# 8chADC_V2.net
KiCad netlist of a schematic drawn in EAGLE
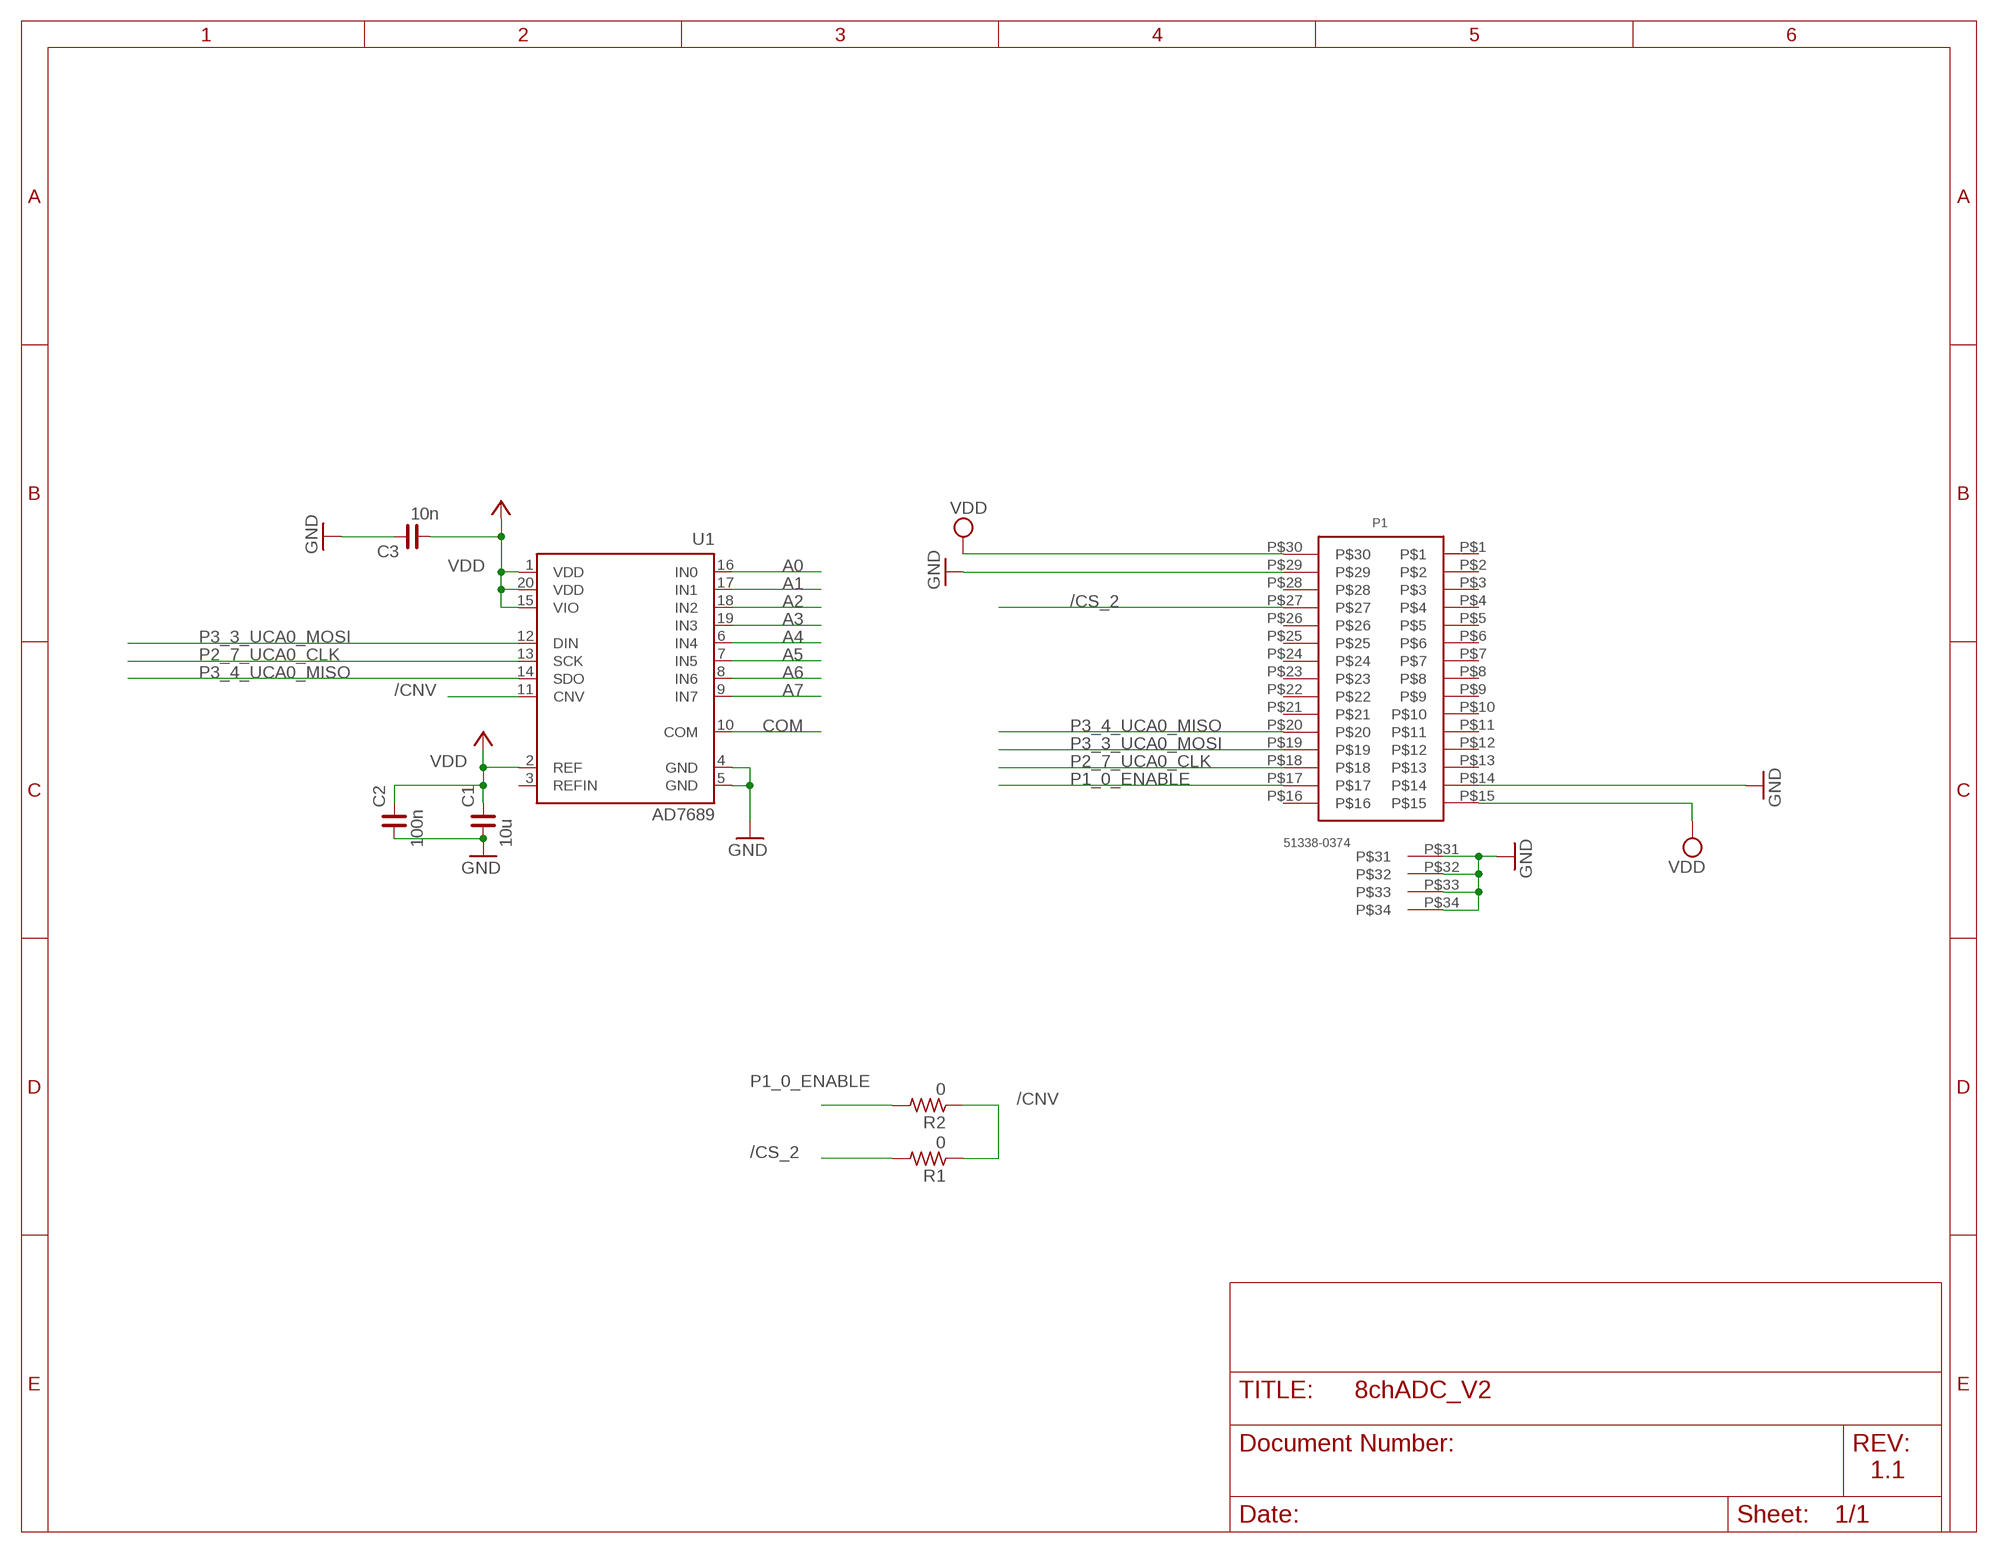
[diagram p0: schematic, sheet 1]

(export (version "E")
  (design (tool "Eeschema 10.0.6"))
  (components
    (comp (ref "C1")
      (value "10u")
      (footprint "eagle-import:C0402")
      (libsource (lib "eagle-import") (part "C_0402"))
    )
    (comp (ref "C2")
      (value "100n")
      (footprint "eagle-import:C0402")
      (libsource (lib "eagle-import") (part "C_0402"))
    )
    (comp (ref "C3")
      (value "10n")
      (footprint "eagle-import:C0402")
      (libsource (lib "eagle-import") (part "C_0402"))
    )
    (comp (ref "P1")
      (value "51338-0374")
      (footprint "eagle-import:51338-0374_RECEPTACLE")
      (libsource (lib "eagle-import") (part "51338-0374_RECEPTACLE"))
    )
    (comp (ref "R1")
      (value "0")
      (footprint "eagle-import:R0402")
      (libsource (lib "eagle-import") (part "R_0402"))
    )
    (comp (ref "R2")
      (value "0")
      (footprint "eagle-import:R0402")
      (libsource (lib "eagle-import") (part "R_0402"))
    )
    (comp (ref "U1")
      (value "AD7689")
      (footprint "eagle-import:LFCSP20")
      (libsource (lib "eagle-import") (part "AD7689"))
    )
  )
  (nets
    (net (code "1") (name "+3V3") (class "Default")
      (node (ref "C1") (pin "2") (pinfunction "2_2") (pintype "passive"))
      (node (ref "C2") (pin "2") (pinfunction "2_2") (pintype "passive"))
      (node (ref "C3") (pin "1") (pinfunction "1_1") (pintype "passive"))
      (node (ref "P1") (pin "P$15") (pinfunction "P$15_P$15") (pintype "bidirectional"))
      (node (ref "P1") (pin "P$30") (pinfunction "P$30_P$30") (pintype "bidirectional"))
      (node (ref "U1") (pin "1") (pinfunction "VDD_1") (pintype "power_in"))
      (node (ref "U1") (pin "15") (pinfunction "VIO_15") (pintype "power_in"))
      (node (ref "U1") (pin "2") (pinfunction "REF_2") (pintype "bidirectional"))
      (node (ref "U1") (pin "20") (pinfunction "VDD_20") (pintype "power_in"))
    )
    (net (code "2") (name "/A0") (class "Default")
      (node (ref "U1") (pin "16") (pinfunction "IN0_16") (pintype "input"))
    )
    (net (code "3") (name "/A1") (class "Default")
      (node (ref "U1") (pin "17") (pinfunction "IN1_17") (pintype "input"))
    )
    (net (code "4") (name "/A2") (class "Default")
      (node (ref "U1") (pin "18") (pinfunction "IN2_18") (pintype "input"))
    )
    (net (code "5") (name "/A3") (class "Default")
      (node (ref "U1") (pin "19") (pinfunction "IN3_19") (pintype "input"))
    )
    (net (code "6") (name "/A4") (class "Default")
      (node (ref "U1") (pin "6") (pinfunction "IN4_6") (pintype "input"))
    )
    (net (code "7") (name "/A5") (class "Default")
      (node (ref "U1") (pin "7") (pinfunction "IN5_7") (pintype "input"))
    )
    (net (code "8") (name "/A6") (class "Default")
      (node (ref "U1") (pin "8") (pinfunction "IN6_8") (pintype "input"))
    )
    (net (code "9") (name "/A7") (class "Default")
      (node (ref "U1") (pin "9") (pinfunction "IN7_9") (pintype "input"))
    )
    (net (code "10") (name "/COM") (class "Default")
      (node (ref "U1") (pin "10") (pinfunction "COM_10") (pintype "input"))
    )
    (net (code "11") (name "/P1_0_ENABLE") (class "Default")
      (node (ref "P1") (pin "P$17") (pinfunction "P$17_P$17") (pintype "bidirectional"))
      (node (ref "R2") (pin "2") (pinfunction "2_2") (pintype "passive"))
    )
    (net (code "12") (name "/P2_7_UCA0_CLK") (class "Default")
      (node (ref "P1") (pin "P$18") (pinfunction "P$18_P$18") (pintype "bidirectional"))
      (node (ref "U1") (pin "13") (pinfunction "SCK_13") (pintype "input"))
    )
    (net (code "13") (name "/P3_3_UCA0_MOSI") (class "Default")
      (node (ref "P1") (pin "P$19") (pinfunction "P$19_P$19") (pintype "bidirectional"))
      (node (ref "U1") (pin "12") (pinfunction "DIN_12") (pintype "input"))
    )
    (net (code "14") (name "/P3_4_UCA0_MISO") (class "Default")
      (node (ref "P1") (pin "P$20") (pinfunction "P$20_P$20") (pintype "bidirectional"))
      (node (ref "U1") (pin "14") (pinfunction "SDO_14") (pintype "output"))
    )
    (net (code "15") (name "/{slash}CNV") (class "Default")
      (node (ref "R1") (pin "1") (pinfunction "1_1") (pintype "passive"))
      (node (ref "R2") (pin "1") (pinfunction "1_1") (pintype "passive"))
      (node (ref "U1") (pin "11") (pinfunction "CNV_11") (pintype "input"))
    )
    (net (code "16") (name "/{slash}CS_2") (class "Default")
      (node (ref "P1") (pin "P$27") (pinfunction "P$27_P$27") (pintype "bidirectional"))
      (node (ref "R1") (pin "2") (pinfunction "2_2") (pintype "passive"))
    )
    (net (code "17") (name "GND") (class "Default")
      (node (ref "C1") (pin "1") (pinfunction "1_1") (pintype "passive"))
      (node (ref "C2") (pin "1") (pinfunction "1_1") (pintype "passive"))
      (node (ref "C3") (pin "2") (pinfunction "2_2") (pintype "passive"))
      (node (ref "P1") (pin "P$14") (pinfunction "P$14_P$14") (pintype "bidirectional"))
      (node (ref "P1") (pin "P$29") (pinfunction "P$29_P$29") (pintype "bidirectional"))
      (node (ref "P1") (pin "P$31") (pinfunction "P$31_P$31") (pintype "bidirectional"))
      (node (ref "P1") (pin "P$32") (pinfunction "P$32_P$32") (pintype "bidirectional"))
      (node (ref "P1") (pin "P$33") (pinfunction "P$33_P$33") (pintype "bidirectional"))
      (node (ref "P1") (pin "P$34") (pinfunction "P$34_P$34") (pintype "bidirectional"))
      (node (ref "U1") (pin "4") (pinfunction "GND_4") (pintype "power_in"))
      (node (ref "U1") (pin "5") (pinfunction "GND_5") (pintype "power_in"))
    )
    (net (code "18") (name "unconnected-(P1-PadP$1)") (class "Default")
      (node (ref "P1") (pin "P$1") (pinfunction "P$1_P$1") (pintype "bidirectional"))
    )
    (net (code "19") (name "unconnected-(P1-PadP$2)") (class "Default")
      (node (ref "P1") (pin "P$2") (pinfunction "P$2_P$2") (pintype "bidirectional"))
    )
    (net (code "20") (name "unconnected-(P1-PadP$3)") (class "Default")
      (node (ref "P1") (pin "P$3") (pinfunction "P$3_P$3") (pintype "bidirectional"))
    )
    (net (code "21") (name "unconnected-(P1-PadP$4)") (class "Default")
      (node (ref "P1") (pin "P$4") (pinfunction "P$4_P$4") (pintype "bidirectional"))
    )
    (net (code "22") (name "unconnected-(P1-PadP$5)") (class "Default")
      (node (ref "P1") (pin "P$5") (pinfunction "P$5_P$5") (pintype "bidirectional"))
    )
    (net (code "23") (name "unconnected-(P1-PadP$6)") (class "Default")
      (node (ref "P1") (pin "P$6") (pinfunction "P$6_P$6") (pintype "bidirectional"))
    )
    (net (code "24") (name "unconnected-(P1-PadP$7)") (class "Default")
      (node (ref "P1") (pin "P$7") (pinfunction "P$7_P$7") (pintype "bidirectional"))
    )
    (net (code "25") (name "unconnected-(P1-PadP$8)") (class "Default")
      (node (ref "P1") (pin "P$8") (pinfunction "P$8_P$8") (pintype "bidirectional"))
    )
    (net (code "26") (name "unconnected-(P1-PadP$9)") (class "Default")
      (node (ref "P1") (pin "P$9") (pinfunction "P$9_P$9") (pintype "bidirectional"))
    )
    (net (code "27") (name "unconnected-(P1-PadP$10)") (class "Default")
      (node (ref "P1") (pin "P$10") (pinfunction "P$10_P$10") (pintype "bidirectional"))
    )
    (net (code "28") (name "unconnected-(P1-PadP$11)") (class "Default")
      (node (ref "P1") (pin "P$11") (pinfunction "P$11_P$11") (pintype "bidirectional"))
    )
    (net (code "29") (name "unconnected-(P1-PadP$12)") (class "Default")
      (node (ref "P1") (pin "P$12") (pinfunction "P$12_P$12") (pintype "bidirectional"))
    )
    (net (code "30") (name "unconnected-(P1-PadP$13)") (class "Default")
      (node (ref "P1") (pin "P$13") (pinfunction "P$13_P$13") (pintype "bidirectional"))
    )
    (net (code "31") (name "unconnected-(P1-PadP$16)") (class "Default")
      (node (ref "P1") (pin "P$16") (pinfunction "P$16_P$16") (pintype "bidirectional"))
    )
    (net (code "32") (name "unconnected-(P1-PadP$21)") (class "Default")
      (node (ref "P1") (pin "P$21") (pinfunction "P$21_P$21") (pintype "bidirectional"))
    )
    (net (code "33") (name "unconnected-(P1-PadP$22)") (class "Default")
      (node (ref "P1") (pin "P$22") (pinfunction "P$22_P$22") (pintype "bidirectional"))
    )
    (net (code "34") (name "unconnected-(P1-PadP$23)") (class "Default")
      (node (ref "P1") (pin "P$23") (pinfunction "P$23_P$23") (pintype "bidirectional"))
    )
    (net (code "35") (name "unconnected-(P1-PadP$24)") (class "Default")
      (node (ref "P1") (pin "P$24") (pinfunction "P$24_P$24") (pintype "bidirectional"))
    )
    (net (code "36") (name "unconnected-(P1-PadP$25)") (class "Default")
      (node (ref "P1") (pin "P$25") (pinfunction "P$25_P$25") (pintype "bidirectional"))
    )
    (net (code "37") (name "unconnected-(P1-PadP$26)") (class "Default")
      (node (ref "P1") (pin "P$26") (pinfunction "P$26_P$26") (pintype "bidirectional"))
    )
    (net (code "38") (name "unconnected-(P1-PadP$28)") (class "Default")
      (node (ref "P1") (pin "P$28") (pinfunction "P$28_P$28") (pintype "bidirectional"))
    )
    (net (code "39") (name "unconnected-(U1-REFIN-Pad3)") (class "Default")
      (node (ref "U1") (pin "3") (pinfunction "REFIN_3") (pintype "bidirectional"))
    )
  )
)
